# Power.net
KiCad netlist of a schematic drawn in Altium Designer
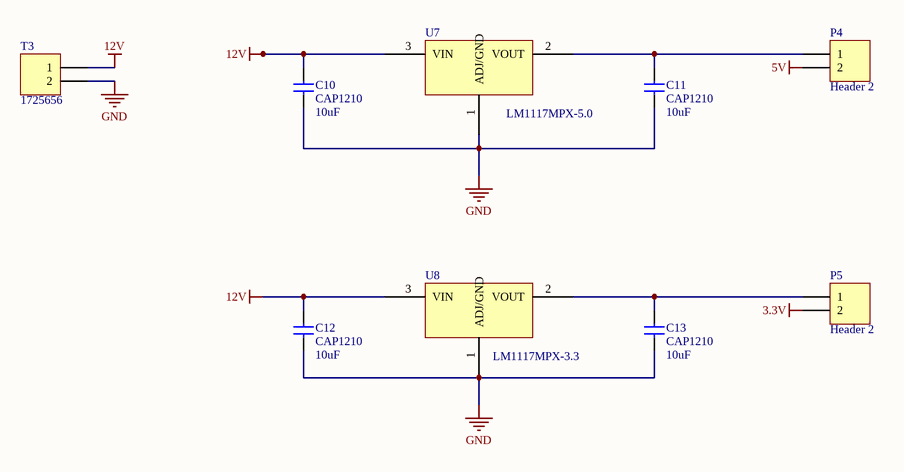
[diagram p0: Power.SchDoc]

(export (version "E")
  (design (tool "Eeschema 10.0.6"))
  (components
    (comp (ref "C10")
      (value "CAP1210")
      (footprint "CAP1210")
      (description "CAP CER 10UF 50V 20% X5R 1210")
      (fields (field (name "ALTIUM_VALUE") "10uF"))
      (libsource (lib "Passives") (part "CAP1210"))
    )
    (comp (ref "C11")
      (value "CAP1210")
      (footprint "CAP1210")
      (description "CAP CER 10UF 50V 20% X5R 1210")
      (fields (field (name "ALTIUM_VALUE") "10uF"))
      (libsource (lib "Passives") (part "CAP1210"))
    )
    (comp (ref "C12")
      (value "CAP1210")
      (footprint "CAP1210")
      (description "CAP CER 10UF 50V 20% X5R 1210")
      (fields (field (name "ALTIUM_VALUE") "10uF"))
      (libsource (lib "Passives") (part "CAP1210"))
    )
    (comp (ref "C13")
      (value "CAP1210")
      (footprint "CAP1210")
      (description "CAP CER 10UF 50V 20% X5R 1210")
      (fields (field (name "ALTIUM_VALUE") "10uF"))
      (libsource (lib "Passives") (part "CAP1210"))
    )
    (comp (ref "P4")
      (value "Header 2")
      (footprint "HDR1X2")
      (description "Header, 2-Pin")
      (fields (field (name "PUBLISHER") "Altium Limited"))
      (libsource (lib "Miscellaneous Connectors") (part "Header 2"))
    )
    (comp (ref "P5")
      (value "Header 2")
      (footprint "HDR1X2")
      (description "Header, 2-Pin")
      (fields (field (name "PUBLISHER") "Altium Limited"))
      (libsource (lib "Miscellaneous Connectors") (part "Header 2"))
    )
    (comp (ref "T3")
      (value "1725656")
      (footprint "1725656")
      (description "CONN TERM BLOCK 2.54MM 2POS")
      (libsource (lib "Sonar_Library") (part "1725656"))
    )
    (comp (ref "U7")
      (value "LM1117MPX-5.0")
      (footprint "LM1117MPX")
      (description "IC REG LDO 5V 0.8A SOT223")
      (libsource (lib "Sonar_Library") (part "LM1117MPX-5"))
    )
    (comp (ref "U8")
      (value "LM1117MPX-3.3")
      (footprint "LM1117MPX")
      (description "IC REG LDO 3.3V 0.8A SOT223")
      (libsource (lib "Sonar_Library") (part "LM1117MPX-3.3"))
    )
  )
  (nets
    (net (code "1") (name "3.3V") (class "Default")
      (node (ref "P5") (pin "2") (pinfunction "2_2") (pintype "passive"))
    )
    (net (code "2") (name "5V") (class "Default")
      (node (ref "P4") (pin "2") (pinfunction "2_2") (pintype "passive"))
    )
    (net (code "3") (name "12V") (class "Default")
      (node (ref "C10") (pin "1") (pinfunction "A_1") (pintype "passive"))
      (node (ref "C12") (pin "1") (pinfunction "A_1") (pintype "passive"))
      (node (ref "T3") (pin "1") (pinfunction "1_1") (pintype "passive"))
      (node (ref "U7") (pin "3") (pinfunction "VIN_3") (pintype "passive"))
      (node (ref "U8") (pin "3") (pinfunction "VIN_3") (pintype "passive"))
    )
    (net (code "4") (name "GND") (class "Default")
      (node (ref "C10") (pin "2") (pinfunction "B_2") (pintype "passive"))
      (node (ref "C11") (pin "2") (pinfunction "B_2") (pintype "passive"))
      (node (ref "C12") (pin "2") (pinfunction "B_2") (pintype "passive"))
      (node (ref "C13") (pin "2") (pinfunction "B_2") (pintype "passive"))
      (node (ref "T3") (pin "2") (pinfunction "2_2") (pintype "passive"))
      (node (ref "U7") (pin "1") (pinfunction "ADJ/GND_1") (pintype "passive"))
      (node (ref "U8") (pin "1") (pinfunction "ADJ/GND_1") (pintype "passive"))
    )
    (net (code "5") (name "Net-(C11-A)") (class "Default")
      (node (ref "C11") (pin "1") (pinfunction "A_1") (pintype "passive"))
      (node (ref "P4") (pin "1") (pinfunction "1_1") (pintype "passive"))
      (node (ref "U7") (pin "2") (pinfunction "VOUT_2") (pintype "passive"))
    )
    (net (code "6") (name "Net-(C13-A)") (class "Default")
      (node (ref "C13") (pin "1") (pinfunction "A_1") (pintype "passive"))
      (node (ref "P5") (pin "1") (pinfunction "1_1") (pintype "passive"))
      (node (ref "U8") (pin "2") (pinfunction "VOUT_2") (pintype "passive"))
    )
  )
)
